# DOORLOCK_v2.net
KiCad netlist of a schematic drawn in EAGLE
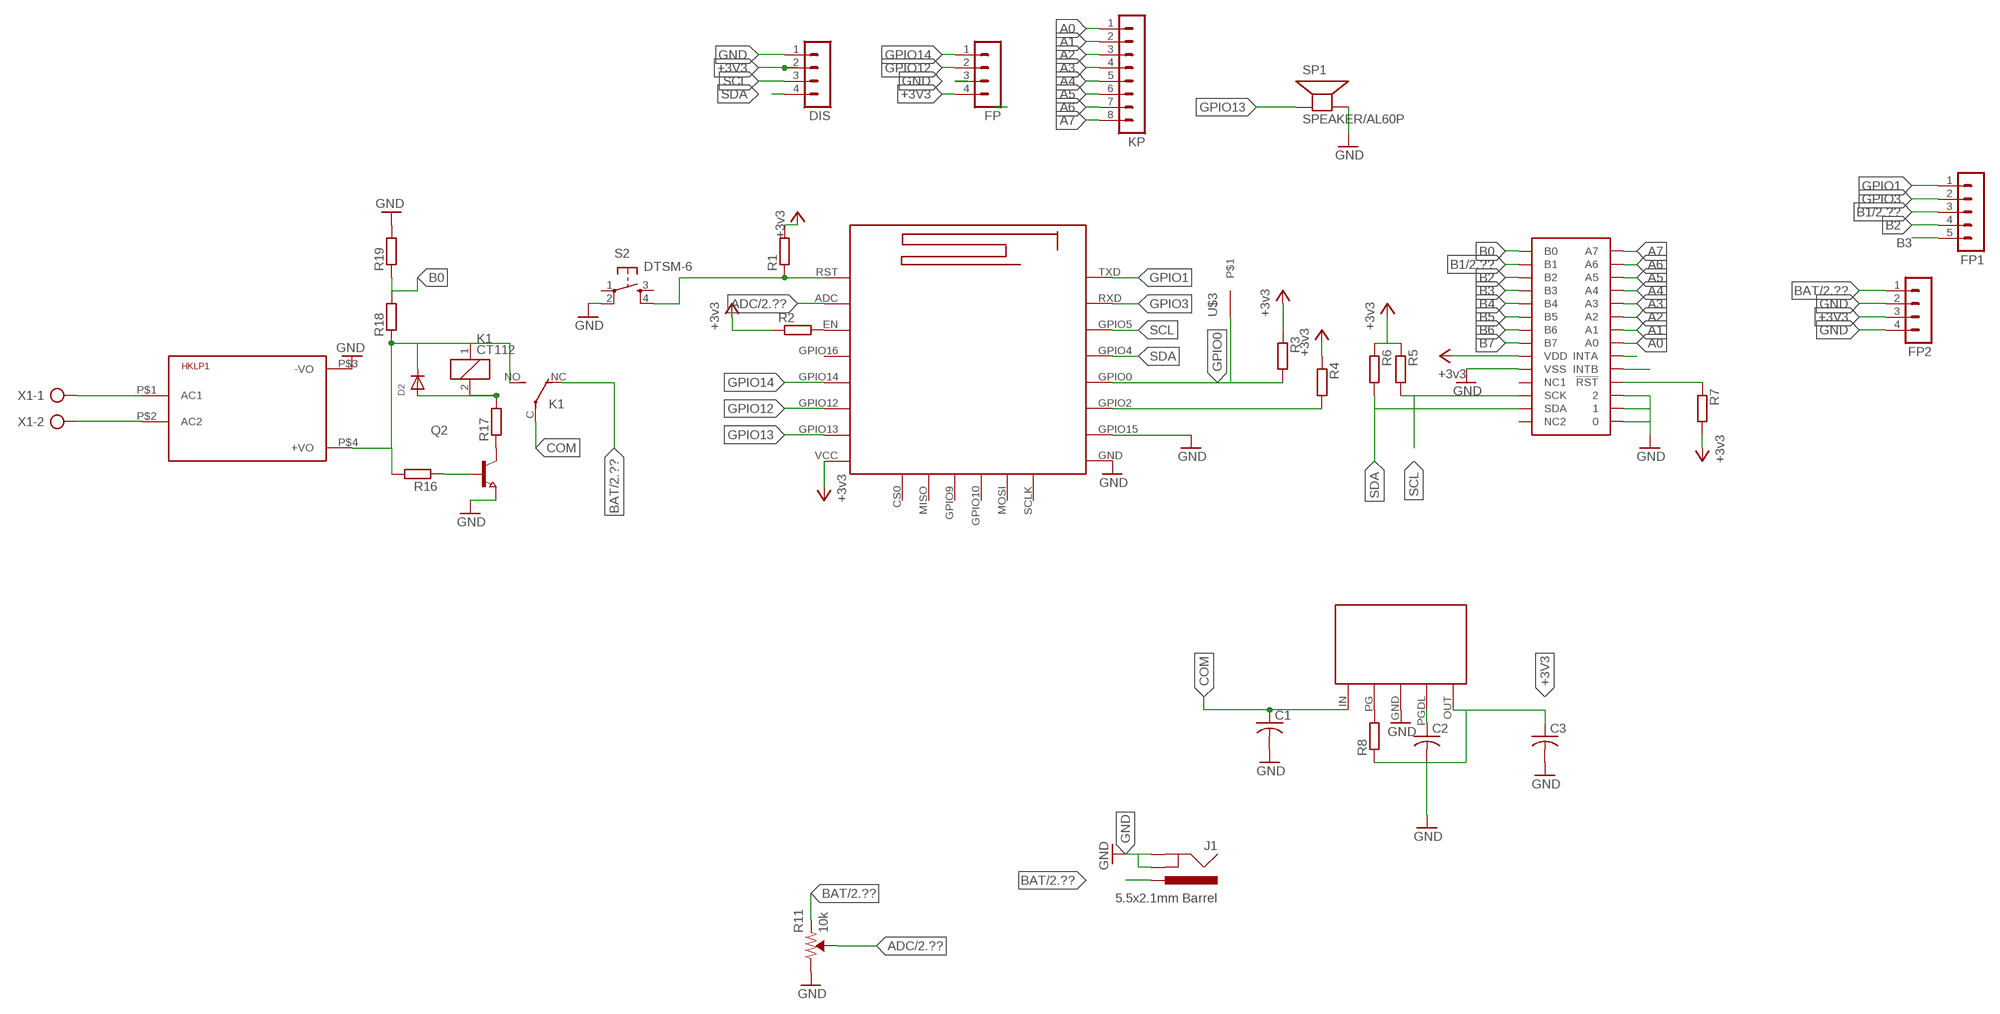
[diagram p0: schematic, sheet 1]
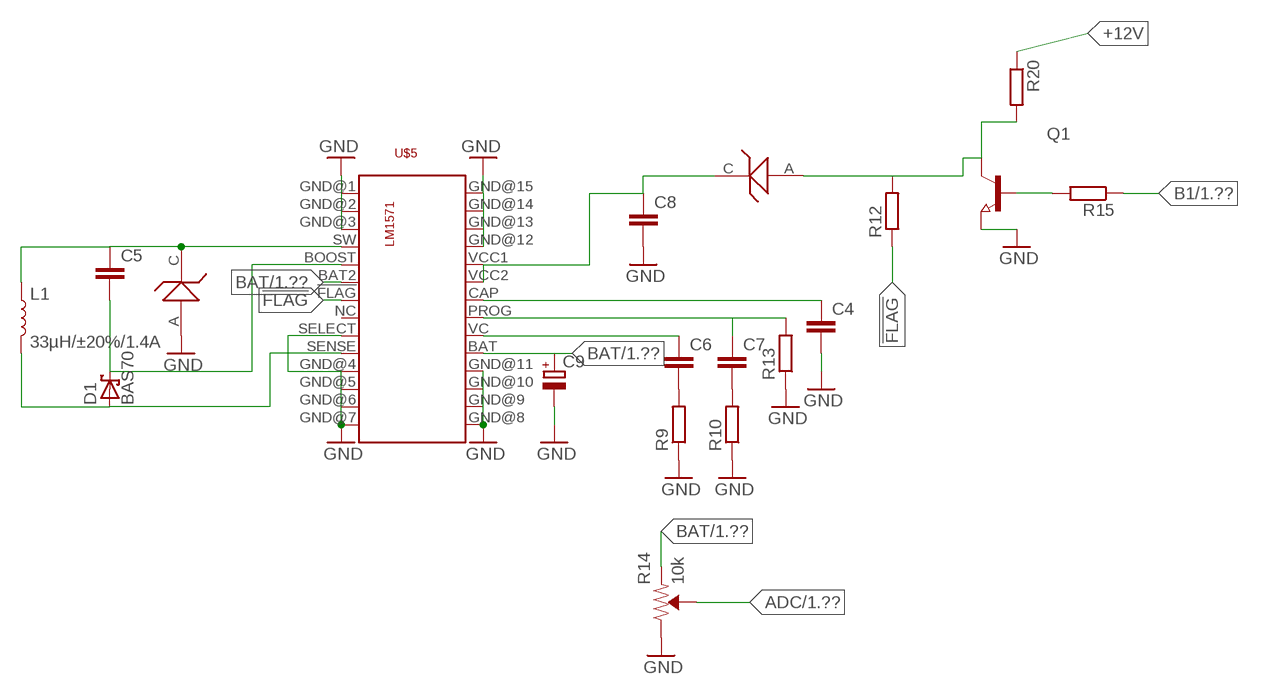
[diagram p1: schematic, sheet 2]

(export (version "E")
  (design (tool "Eeschema 10.0.6"))
  (components
    (comp (ref "C1")
      (value "C-USC1206")
      (footprint "eagle-import:C1206")
      (libsource (lib "eagle-import") (part "C-USC1206"))
    )
    (comp (ref "C2")
      (value "C-USC1206")
      (footprint "eagle-import:C1206")
      (libsource (lib "eagle-import") (part "C-USC1206"))
    )
    (comp (ref "C3")
      (value "C-USC1206")
      (footprint "eagle-import:C1206")
      (libsource (lib "eagle-import") (part "C-USC1206"))
    )
    (comp (ref "D2")
      (value "DIODESOD-123")
      (footprint "eagle-import:SOD-123")
      (libsource (lib "eagle-import") (part "DIODESOD-123"))
    )
    (comp (ref "DIS")
      (value "MA04-1")
      (footprint "eagle-import:MA04-1")
      (libsource (lib "eagle-import") (part "MA04-1"))
    )
    (comp (ref "FP")
      (value "MA04-1")
      (footprint "eagle-import:MA04-1")
      (libsource (lib "eagle-import") (part "MA04-1"))
    )
    (comp (ref "FP1")
      (value "MA05-1")
      (footprint "eagle-import:MA05-1")
      (libsource (lib "eagle-import") (part "MA05-1"))
    )
    (comp (ref "FP2")
      (value "MA04-1")
      (footprint "eagle-import:MA04-1")
      (libsource (lib "eagle-import") (part "MA04-1"))
    )
    (comp (ref "HKLP1")
      (value "HKLPM01")
      (footprint "eagle-import:HKLPM01")
      (libsource (lib "eagle-import") (part "HKLPM01"))
    )
    (comp (ref "J1")
      (value "5.5x2.1mm Barrel")
      (footprint "eagle-import:POWER_JACK_SMD")
      (libsource (lib "eagle-import") (part "POWER_JACKSMD"))
    )
    (comp (ref "K1")
      (value "CT112")
      (footprint "eagle-import:CT-SLIM")
      (libsource (lib "eagle-import") (part "CT112"))
    )
    (comp (ref "KP")
      (value "MA08-1")
      (footprint "eagle-import:MA08-1")
      (libsource (lib "eagle-import") (part "MA08-1"))
    )
    (comp (ref "Q2")
      (value "NPN-TRANSISTOR_SOT89")
      (footprint "eagle-import:SOT89")
      (libsource (lib "eagle-import") (part "NPN-TRANSISTOR_SOT89"))
    )
    (comp (ref "R1")
      (value "R-EU_0204/2V")
      (footprint "eagle-import:0204V")
      (libsource (lib "eagle-import") (part "resistor_R-EU_0204/2V"))
    )
    (comp (ref "R2")
      (value "R-EU_0204/2V")
      (footprint "eagle-import:0204V")
      (libsource (lib "eagle-import") (part "resistor_R-EU_0204/2V"))
    )
    (comp (ref "R3")
      (value "R-EU_0204/2V")
      (footprint "eagle-import:0204V")
      (libsource (lib "eagle-import") (part "resistor_R-EU_0204/2V"))
    )
    (comp (ref "R4")
      (value "R-EU_0204/2V")
      (footprint "eagle-import:0204V")
      (libsource (lib "eagle-import") (part "resistor_R-EU_0204/2V"))
    )
    (comp (ref "R5")
      (value "R-EU_0204/2V")
      (footprint "eagle-import:0204V")
      (libsource (lib "eagle-import") (part "resistor_R-EU_0204/2V"))
    )
    (comp (ref "R6")
      (value "R-EU_0204/2V")
      (footprint "eagle-import:0204V")
      (libsource (lib "eagle-import") (part "resistor_R-EU_0204/2V"))
    )
    (comp (ref "R7")
      (value "R-EU_0204/2V")
      (footprint "eagle-import:0204V")
      (libsource (lib "eagle-import") (part "resistor_R-EU_0204/2V"))
    )
    (comp (ref "R8")
      (value "R-EU_0204/2V")
      (footprint "eagle-import:0204V")
      (libsource (lib "eagle-import") (part "resistor_R-EU_0204/2V"))
    )
    (comp (ref "R11")
      (value "10k")
      (footprint "eagle-import:TRIMPOT-SMD-TC33X")
      (libsource (lib "eagle-import") (part "TRIMPOT-SMD-3MM-OPEN-1/10W-25%"))
    )
    (comp (ref "R16")
      (value "R-EU_0204/2V")
      (footprint "eagle-import:0204V")
      (libsource (lib "eagle-import") (part "resistor_R-EU_0204/2V"))
    )
    (comp (ref "R17")
      (value "R-EU_0204/2V")
      (footprint "eagle-import:0204V")
      (libsource (lib "eagle-import") (part "resistor_R-EU_0204/2V"))
    )
    (comp (ref "R18")
      (value "R-EU_0204/2V")
      (footprint "eagle-import:0204V")
      (libsource (lib "eagle-import") (part "resistor_R-EU_0204/2V"))
    )
    (comp (ref "R19")
      (value "R-EU_0204/2V")
      (footprint "eagle-import:0204V")
      (libsource (lib "eagle-import") (part "resistor_R-EU_0204/2V"))
    )
    (comp (ref "S2")
      (value "DTSM-6")
      (footprint "eagle-import:DTSM-6")
      (libsource (lib "eagle-import") (part "DTSM-6"))
    )
    (comp (ref "SP1")
      (value "SPEAKER/AL60P")
      (footprint "eagle-import:AL60P")
      (libsource (lib "eagle-import") (part "SPEAKER/AL60P"))
    )
    (comp (ref "U$1")
      (value "ESP12E")
      (footprint "eagle-import:ESP-12E")
      (libsource (lib "eagle-import") (part "ESP12E"))
    )
    (comp (ref "U$2")
      (value "MCF23017")
      (footprint "eagle-import:MAX23017")
      (libsource (lib "eagle-import") (part "MCF23017"))
    )
    (comp (ref "U$3") (value "M1") (footprint "eagle-import:M1") (libsource (lib "eagle-import") (part "M1")))
    (comp (ref "U$4")
      (value "MP2014")
      (footprint "eagle-import:MP2014")
      (libsource (lib "eagle-import") (part "MP2014"))
    )
    (comp (ref "X1")
      (value "AK500/2-H")
      (footprint "eagle-import:AK500_2-H")
      (libsource (lib "eagle-import") (part "AK500/2-H"))
    )
    (comp (ref "C4")
      (value "C-EUC0805")
      (footprint "eagle-import:C0805")
      (libsource (lib "eagle-import") (part "C-EUC0805"))
    )
    (comp (ref "C5")
      (value "C-EUC0805")
      (footprint "eagle-import:C0805")
      (libsource (lib "eagle-import") (part "C-EUC0805"))
    )
    (comp (ref "C6")
      (value "C-EUC0805")
      (footprint "eagle-import:C0805")
      (libsource (lib "eagle-import") (part "C-EUC0805"))
    )
    (comp (ref "C7")
      (value "C-EUC0805")
      (footprint "eagle-import:C0805")
      (libsource (lib "eagle-import") (part "C-EUC0805"))
    )
    (comp (ref "C8")
      (value "C-EUC0805")
      (footprint "eagle-import:C0805")
      (libsource (lib "eagle-import") (part "C-EUC0805"))
    )
    (comp (ref "C9")
      (value "CPOL-EUCT3216")
      (footprint "eagle-import:CT3216")
      (libsource (lib "eagle-import") (part "CPOL-EUCT3216"))
    )
    (comp (ref "D1")
      (value "BAS70")
      (footprint "eagle-import:SOT23")
      (libsource (lib "eagle-import") (part "BAS70"))
    )
    (comp (ref "D3")
      (value "MBRM120T3")
      (footprint "eagle-import:MBRM120T3")
      (libsource (lib "eagle-import") (part "MBRM120T3"))
    )
    (comp (ref "L1")
      (value "33µH/±20%/1.4A")
      (footprint "eagle-import:SRN6045")
      (libsource (lib "eagle-import") (part "INDUCTOR-SRN6045-33UH"))
    )
    (comp (ref "Q1")
      (value "NPN-TRANSISTOR_SOT89")
      (footprint "eagle-import:SOT89")
      (libsource (lib "eagle-import") (part "NPN-TRANSISTOR_SOT89"))
    )
    (comp (ref "R9")
      (value "R-EU_0204/2V")
      (footprint "eagle-import:0204V")
      (libsource (lib "eagle-import") (part "R-EU_0204/2V"))
    )
    (comp (ref "R10")
      (value "R-EU_0204/2V")
      (footprint "eagle-import:0204V")
      (libsource (lib "eagle-import") (part "R-EU_0204/2V"))
    )
    (comp (ref "R12")
      (value "R-EU_0204/2V")
      (footprint "eagle-import:0204V")
      (libsource (lib "eagle-import") (part "R-EU_0204/2V"))
    )
    (comp (ref "R13")
      (value "R-EU_0204/2V")
      (footprint "eagle-import:0204V")
      (libsource (lib "eagle-import") (part "R-EU_0204/2V"))
    )
    (comp (ref "R14")
      (value "10k")
      (footprint "eagle-import:TRIMPOT-SMD-TC33X")
      (libsource (lib "eagle-import") (part "TRIMPOT-SMD-3MM-OPEN-1/10W-25%"))
    )
    (comp (ref "R15")
      (value "R-EU_0204/2V")
      (footprint "eagle-import:0204V")
      (libsource (lib "eagle-import") (part "R-EU_0204/2V"))
    )
    (comp (ref "R20")
      (value "R-EU_0204/2V")
      (footprint "eagle-import:0204V")
      (libsource (lib "eagle-import") (part "R-EU_0204/2V"))
    )
    (comp (ref "U$5")
      (value "LM1571")
      (footprint "eagle-import:LT1571")
      (libsource (lib "eagle-import") (part "LM1571"))
    )
    (comp (ref "U$6")
      (value "MBRM120T3")
      (footprint "eagle-import:MBRM120T3")
      (libsource (lib "eagle-import") (part "MBRM120T3"))
    )
  )
  (nets
    (net (code "1") (name "+3V3") (class "Default")
      (node (ref "C3") (pin "1") (pinfunction "1_1") (pintype "passive"))
      (node (ref "DIS") (pin "2") (pinfunction "2_2") (pintype "passive"))
      (node (ref "FP") (pin "4") (pinfunction "4_4") (pintype "passive"))
      (node (ref "FP2") (pin "3") (pinfunction "3_3") (pintype "passive"))
      (node (ref "R1") (pin "2") (pinfunction "2_2") (pintype "passive"))
      (node (ref "R2") (pin "1") (pinfunction "1_1") (pintype "passive"))
      (node (ref "R3") (pin "1") (pinfunction "1_1") (pintype "passive"))
      (node (ref "R4") (pin "1") (pinfunction "1_1") (pintype "passive"))
      (node (ref "R5") (pin "1") (pinfunction "1_1") (pintype "passive"))
      (node (ref "R6") (pin "1") (pinfunction "1_1") (pintype "passive"))
      (node (ref "R7") (pin "2") (pinfunction "2_2") (pintype "passive"))
      (node (ref "R8") (pin "1") (pinfunction "1_1") (pintype "passive"))
      (node (ref "U$1") (pin "VCC") (pinfunction "P$8_VCC") (pintype "bidirectional"))
      (node (ref "U$2") (pin "P$9") (pinfunction "VDD_P$9") (pintype "bidirectional"))
      (node (ref "U$4") (pin "OUT") (pinfunction "P$5_OUT") (pintype "bidirectional"))
    )
    (net (code "2") (name "+12V") (class "Default")
      (node (ref "D2") (pin "C") (pinfunction "C_C") (pintype "passive"))
      (node (ref "HKLP1") (pin "P$4") (pinfunction "+VO_P$4") (pintype "bidirectional"))
      (node (ref "K1") (pin "1") (pinfunction "1_1") (pintype "passive"))
      (node (ref "K1") (pin "NO") (pinfunction "S_NO") (pintype "passive"))
      (node (ref "R16") (pin "2") (pinfunction "2_2") (pintype "passive"))
      (node (ref "R18") (pin "1") (pinfunction "1_1") (pintype "passive"))
      (node (ref "R20") (pin "1") (pinfunction "1_1") (pintype "passive"))
    )
    (net (code "3") (name "A0") (class "Default")
      (node (ref "KP") (pin "1") (pinfunction "1_1") (pintype "passive"))
      (node (ref "U$2") (pin "P$21") (pinfunction "A0_P$21") (pintype "bidirectional"))
    )
    (net (code "4") (name "A1") (class "Default")
      (node (ref "KP") (pin "2") (pinfunction "2_2") (pintype "passive"))
      (node (ref "U$2") (pin "P$22") (pinfunction "A1_P$22") (pintype "bidirectional"))
    )
    (net (code "5") (name "A2") (class "Default")
      (node (ref "KP") (pin "3") (pinfunction "3_3") (pintype "passive"))
      (node (ref "U$2") (pin "P$23") (pinfunction "A2_P$23") (pintype "bidirectional"))
    )
    (net (code "6") (name "A3") (class "Default")
      (node (ref "KP") (pin "4") (pinfunction "4_4") (pintype "passive"))
      (node (ref "U$2") (pin "P$24") (pinfunction "A3_P$24") (pintype "bidirectional"))
    )
    (net (code "7") (name "A4") (class "Default")
      (node (ref "KP") (pin "5") (pinfunction "5_5") (pintype "passive"))
      (node (ref "U$2") (pin "P$25") (pinfunction "A4_P$25") (pintype "bidirectional"))
    )
    (net (code "8") (name "A5") (class "Default")
      (node (ref "KP") (pin "6") (pinfunction "6_6") (pintype "passive"))
      (node (ref "U$2") (pin "P$26") (pinfunction "A5_P$26") (pintype "bidirectional"))
    )
    (net (code "9") (name "A6") (class "Default")
      (node (ref "KP") (pin "7") (pinfunction "7_7") (pintype "passive"))
      (node (ref "U$2") (pin "P$27") (pinfunction "A6_P$27") (pintype "bidirectional"))
    )
    (net (code "10") (name "A7") (class "Default")
      (node (ref "KP") (pin "8") (pinfunction "8_8") (pintype "passive"))
      (node (ref "U$2") (pin "P$28") (pinfunction "A7_P$28") (pintype "bidirectional"))
    )
    (net (code "11") (name "ADC") (class "Default")
      (node (ref "R11") (pin "2") (pinfunction "WIPER_2") (pintype "passive"))
      (node (ref "R14") (pin "2") (pinfunction "WIPER_2") (pintype "passive"))
      (node (ref "U$1") (pin "ADC") (pinfunction "P$2_ADC") (pintype "bidirectional"))
    )
    (net (code "12") (name "B0") (class "Default")
      (node (ref "R18") (pin "2") (pinfunction "2_2") (pintype "passive"))
      (node (ref "R19") (pin "1") (pinfunction "1_1") (pintype "passive"))
      (node (ref "U$2") (pin "P$1") (pinfunction "B0_P$1") (pintype "bidirectional"))
    )
    (net (code "13") (name "B1") (class "Default")
      (node (ref "FP1") (pin "3") (pinfunction "3_3") (pintype "passive"))
      (node (ref "R15") (pin "1") (pinfunction "1_1") (pintype "passive"))
      (node (ref "U$2") (pin "P$2") (pinfunction "B1_P$2") (pintype "bidirectional"))
    )
    (net (code "14") (name "B2") (class "Default")
      (node (ref "FP1") (pin "4") (pinfunction "4_4") (pintype "passive"))
      (node (ref "U$2") (pin "P$3") (pinfunction "B2_P$3") (pintype "bidirectional"))
    )
    (net (code "15") (name "B3") (class "Default")
      (node (ref "FP1") (pin "5") (pinfunction "5_5") (pintype "passive"))
      (node (ref "U$2") (pin "P$4") (pinfunction "B3_P$4") (pintype "bidirectional"))
    )
    (net (code "16") (name "B4") (class "Default")
      (node (ref "U$2") (pin "P$5") (pinfunction "B4_P$5") (pintype "bidirectional"))
    )
    (net (code "17") (name "B5") (class "Default")
      (node (ref "U$2") (pin "P$6") (pinfunction "B5_P$6") (pintype "bidirectional"))
    )
    (net (code "18") (name "B6") (class "Default")
      (node (ref "U$2") (pin "P$7") (pinfunction "B6_P$7") (pintype "bidirectional"))
    )
    (net (code "19") (name "B7") (class "Default")
      (node (ref "U$2") (pin "P$8") (pinfunction "B7_P$8") (pintype "bidirectional"))
    )
    (net (code "20") (name "BAT") (class "Default")
      (node (ref "C9") (pin "+") (pinfunction "+_+") (pintype "passive"))
      (node (ref "FP2") (pin "1") (pinfunction "1_1") (pintype "passive"))
      (node (ref "J1") (pin "VIN0") (pinfunction "PWR_VIN0") (pintype "bidirectional"))
      (node (ref "K1") (pin "NC") (pinfunction "O_NC") (pintype "passive"))
      (node (ref "R11") (pin "3") (pinfunction "CCW_3") (pintype "passive"))
      (node (ref "R14") (pin "3") (pinfunction "CCW_3") (pintype "passive"))
      (node (ref "U$5") (pin "BAT") (pinfunction "P$19_BAT") (pintype "bidirectional"))
      (node (ref "U$5") (pin "BAT2") (pinfunction "P$6_BAT2") (pintype "bidirectional"))
    )
    (net (code "21") (name "COM") (class "Default")
      (node (ref "C1") (pin "1") (pinfunction "1_1") (pintype "passive"))
      (node (ref "K1") (pin "C") (pinfunction "P_C") (pintype "passive"))
      (node (ref "U$4") (pin "IN") (pinfunction "P$1_IN") (pintype "bidirectional"))
    )
    (net (code "22") (name "GND") (class "Default")
      (node (ref "C1") (pin "2") (pinfunction "2_2") (pintype "passive"))
      (node (ref "C2") (pin "2") (pinfunction "2_2") (pintype "passive"))
      (node (ref "C3") (pin "2") (pinfunction "2_2") (pintype "passive"))
      (node (ref "C4") (pin "2") (pinfunction "2_2") (pintype "passive"))
      (node (ref "C8") (pin "2") (pinfunction "2_2") (pintype "passive"))
      (node (ref "C9") (pin "-") (pinfunction "-_-") (pintype "passive"))
      (node (ref "DIS") (pin "1") (pinfunction "1_1") (pintype "passive"))
      (node (ref "FP") (pin "3") (pinfunction "3_3") (pintype "passive"))
      (node (ref "FP2") (pin "2") (pinfunction "2_2") (pintype "passive"))
      (node (ref "FP2") (pin "4") (pinfunction "4_4") (pintype "passive"))
      (node (ref "HKLP1") (pin "P$3") (pinfunction "-VO_P$3") (pintype "bidirectional"))
      (node (ref "J1") (pin "GND") (pinfunction "GNDBREAK_GND") (pintype "bidirectional"))
      (node (ref "J1") (pin "P$4") (pinfunction "GND_P$4") (pintype "bidirectional"))
      (node (ref "Q1") (pin "3") (pinfunction "E_3") (pintype "passive"))
      (node (ref "Q2") (pin "3") (pinfunction "E_3") (pintype "passive"))
      (node (ref "R10") (pin "1") (pinfunction "1_1") (pintype "passive"))
      (node (ref "R11") (pin "1") (pinfunction "CW_1") (pintype "passive"))
      (node (ref "R13") (pin "1") (pinfunction "1_1") (pintype "passive"))
      (node (ref "R14") (pin "1") (pinfunction "CW_1") (pintype "passive"))
      (node (ref "R19") (pin "2") (pinfunction "2_2") (pintype "passive"))
      (node (ref "R9") (pin "1") (pinfunction "1_1") (pintype "passive"))
      (node (ref "S2") (pin "2") (pinfunction "2_2") (pintype "passive"))
      (node (ref "SP1") (pin "2") (pinfunction "-_2") (pintype "passive"))
      (node (ref "U$1") (pin "GND") (pinfunction "P$15_GND") (pintype "bidirectional"))
      (node (ref "U$1") (pin "GPIO15") (pinfunction "P$16_GPIO15") (pintype "bidirectional"))
      (node (ref "U$2") (pin "P$10") (pinfunction "VSS_P$10") (pintype "bidirectional"))
      (node (ref "U$2") (pin "P$15") (pinfunction "0_P$15") (pintype "bidirectional"))
      (node (ref "U$2") (pin "P$16") (pinfunction "1_P$16") (pintype "bidirectional"))
      (node (ref "U$2") (pin "P$17") (pinfunction "2_P$17") (pintype "bidirectional"))
      (node (ref "U$4") (pin "GND") (pinfunction "P$3_GND") (pintype "bidirectional"))
      (node (ref "U$5") (pin "GND@1") (pinfunction "P$1_GND@1") (pintype "bidirectional"))
      (node (ref "U$5") (pin "GND@10") (pinfunction "P$17_GND@10") (pintype "bidirectional"))
      (node (ref "U$5") (pin "GND@11") (pinfunction "P$18_GND@11") (pintype "bidirectional"))
      (node (ref "U$5") (pin "GND@12") (pinfunction "P$25_GND@12") (pintype "bidirectional"))
      (node (ref "U$5") (pin "GND@13") (pinfunction "P$26_GND@13") (pintype "bidirectional"))
      (node (ref "U$5") (pin "GND@14") (pinfunction "P$27_GND@14") (pintype "bidirectional"))
      (node (ref "U$5") (pin "GND@15") (pinfunction "P$28_GND@15") (pintype "bidirectional"))
      (node (ref "U$5") (pin "GND@2") (pinfunction "P$2_GND@2") (pintype "bidirectional"))
      (node (ref "U$5") (pin "GND@3") (pinfunction "P$3_GND@3") (pintype "bidirectional"))
      (node (ref "U$5") (pin "GND@4") (pinfunction "P$11_GND@4") (pintype "bidirectional"))
      (node (ref "U$5") (pin "GND@5") (pinfunction "P$12_GND@5") (pintype "bidirectional"))
      (node (ref "U$5") (pin "GND@6") (pinfunction "P$13_GND@6") (pintype "bidirectional"))
      (node (ref "U$5") (pin "GND@7") (pinfunction "P$14_GND@7") (pintype "bidirectional"))
      (node (ref "U$5") (pin "GND@8") (pinfunction "P$15_GND@8") (pintype "bidirectional"))
      (node (ref "U$5") (pin "GND@9") (pinfunction "P$16_GND@9") (pintype "bidirectional"))
      (node (ref "U$5") (pin "SELECT") (pinfunction "P$9_SELECT") (pintype "bidirectional"))
      (node (ref "U$6") (pin "A") (pinfunction "A_A") (pintype "bidirectional"))
    )
    (net (code "23") (name "GPIO0") (class "Default")
      (node (ref "R3") (pin "2") (pinfunction "2_2") (pintype "passive"))
      (node (ref "U$1") (pin "GPIO0") (pinfunction "P$18_GPIO0") (pintype "bidirectional"))
      (node (ref "U$3") (pin "P$1") (pinfunction "P$1_P$1") (pintype "bidirectional"))
    )
    (net (code "24") (name "GPIO1") (class "Default")
      (node (ref "FP1") (pin "1") (pinfunction "1_1") (pintype "passive"))
      (node (ref "U$1") (pin "TXD") (pinfunction "P$22_TXD") (pintype "bidirectional"))
    )
    (net (code "25") (name "GPIO3") (class "Default")
      (node (ref "FP1") (pin "2") (pinfunction "2_2") (pintype "passive"))
      (node (ref "U$1") (pin "RXD") (pinfunction "P$21_RXD") (pintype "bidirectional"))
    )
    (net (code "26") (name "GPIO12") (class "Default")
      (node (ref "FP") (pin "2") (pinfunction "2_2") (pintype "passive"))
      (node (ref "U$1") (pin "GPIO12") (pinfunction "P$6_GPIO12") (pintype "bidirectional"))
    )
    (net (code "27") (name "GPIO13") (class "Default")
      (node (ref "SP1") (pin "1") (pinfunction "+_1") (pintype "passive"))
      (node (ref "U$1") (pin "GPIO13") (pinfunction "P$7_GPIO13") (pintype "bidirectional"))
    )
    (net (code "28") (name "GPIO14") (class "Default")
      (node (ref "FP") (pin "1") (pinfunction "1_1") (pintype "passive"))
      (node (ref "U$1") (pin "GPIO14") (pinfunction "P$5_GPIO14") (pintype "bidirectional"))
    )
    (net (code "29") (name "Net-(C6-Pad2)") (class "Default")
      (node (ref "C6") (pin "2") (pinfunction "2_2") (pintype "passive"))
      (node (ref "R9") (pin "2") (pinfunction "2_2") (pintype "passive"))
    )
    (net (code "30") (name "Net-(C7-Pad2)") (class "Default")
      (node (ref "C7") (pin "2") (pinfunction "2_2") (pintype "passive"))
      (node (ref "R10") (pin "2") (pinfunction "2_2") (pintype "passive"))
    )
    (net (code "31") (name "Net-(D1-A)") (class "Default")
      (node (ref "D1") (pin "1") (pinfunction "A_1") (pintype "passive"))
      (node (ref "L1") (pin "2") (pinfunction "2_2") (pintype "passive"))
      (node (ref "U$5") (pin "SENSE") (pinfunction "P$10_SENSE") (pintype "bidirectional"))
    )
    (net (code "32") (name "Net-(D1-C)") (class "Default")
      (node (ref "C5") (pin "2") (pinfunction "2_2") (pintype "passive"))
      (node (ref "D1") (pin "3") (pinfunction "C_3") (pintype "passive"))
      (node (ref "U$5") (pin "BOOST") (pinfunction "P$5_BOOST") (pintype "bidirectional"))
    )
    (net (code "33") (name "Net-(D2-PadA)") (class "Default")
      (node (ref "D2") (pin "A") (pinfunction "A_A") (pintype "passive"))
      (node (ref "K1") (pin "2") (pinfunction "2_2") (pintype "passive"))
      (node (ref "R17") (pin "2") (pinfunction "2_2") (pintype "passive"))
    )
    (net (code "34") (name "Net-(HKLP1-AC1)") (class "Default")
      (node (ref "HKLP1") (pin "P$1") (pinfunction "AC1_P$1") (pintype "bidirectional"))
      (node (ref "X1") (pin "1") (pinfunction "KL_1") (pintype "passive"))
    )
    (net (code "35") (name "Net-(HKLP1-AC2)") (class "Default")
      (node (ref "HKLP1") (pin "P$2") (pinfunction "AC2_P$2") (pintype "bidirectional"))
      (node (ref "X1") (pin "2") (pinfunction "KL_2") (pintype "passive"))
    )
    (net (code "36") (name "Net-(Q1-B)") (class "Default")
      (node (ref "Q1") (pin "1") (pinfunction "B_1") (pintype "passive"))
      (node (ref "R15") (pin "2") (pinfunction "2_2") (pintype "passive"))
    )
    (net (code "37") (name "Net-(Q1-C)") (class "Default")
      (node (ref "D3") (pin "A") (pinfunction "A_A") (pintype "bidirectional"))
      (node (ref "Q1") (pin "2") (pinfunction "C_2") (pintype "passive"))
      (node (ref "R12") (pin "2") (pinfunction "2_2") (pintype "passive"))
      (node (ref "R20") (pin "2") (pinfunction "2_2") (pintype "passive"))
    )
    (net (code "38") (name "Net-(Q2-B)") (class "Default")
      (node (ref "Q2") (pin "1") (pinfunction "B_1") (pintype "passive"))
      (node (ref "R16") (pin "1") (pinfunction "1_1") (pintype "passive"))
    )
    (net (code "39") (name "Net-(Q2-C)") (class "Default")
      (node (ref "Q2") (pin "2") (pinfunction "C_2") (pintype "passive"))
      (node (ref "R17") (pin "1") (pinfunction "1_1") (pintype "passive"))
    )
    (net (code "40") (name "Net-(U$1-P$1)") (class "Default")
      (node (ref "R1") (pin "1") (pinfunction "1_1") (pintype "passive"))
      (node (ref "S2") (pin "4") (pinfunction "4_4") (pintype "passive"))
      (node (ref "U$1") (pin "RST") (pinfunction "P$1_RST") (pintype "bidirectional"))
    )
    (net (code "41") (name "Net-(U$1-P$3)") (class "Default")
      (node (ref "R2") (pin "2") (pinfunction "2_2") (pintype "passive"))
      (node (ref "U$1") (pin "EN") (pinfunction "P$3_EN") (pintype "bidirectional"))
    )
    (net (code "42") (name "Net-(U$1-P$17)") (class "Default")
      (node (ref "R4") (pin "2") (pinfunction "2_2") (pintype "passive"))
      (node (ref "U$1") (pin "GPIO2") (pinfunction "P$17_GPIO2") (pintype "bidirectional"))
    )
    (net (code "43") (name "Net-(U$2-~{RST})") (class "Default")
      (node (ref "R7") (pin "1") (pinfunction "1_1") (pintype "passive"))
      (node (ref "U$2") (pin "P$18") (pinfunction "~{RST}_P$18") (pintype "bidirectional"))
    )
    (net (code "44") (name "Net-(U$4-P$2)") (class "Default")
      (node (ref "R8") (pin "2") (pinfunction "2_2") (pintype "passive"))
      (node (ref "U$4") (pin "PG") (pinfunction "P$2_PG") (pintype "bidirectional"))
    )
    (net (code "45") (name "Net-(U$4-P$4)") (class "Default")
      (node (ref "C2") (pin "1") (pinfunction "1_1") (pintype "passive"))
      (node (ref "U$4") (pin "PGDL") (pinfunction "P$4_PGDL") (pintype "bidirectional"))
    )
    (net (code "46") (name "Net-(U$5-P$4)") (class "Default")
      (node (ref "C5") (pin "1") (pinfunction "1_1") (pintype "passive"))
      (node (ref "L1") (pin "1") (pinfunction "1_1") (pintype "passive"))
      (node (ref "U$5") (pin "SW") (pinfunction "P$4_SW") (pintype "bidirectional"))
      (node (ref "U$6") (pin "C") (pinfunction "C_C") (pintype "bidirectional"))
    )
    (net (code "47") (name "Net-(U$5-P$20)") (class "Default")
      (node (ref "C6") (pin "1") (pinfunction "1_1") (pintype "passive"))
      (node (ref "U$5") (pin "VC") (pinfunction "P$20_VC") (pintype "bidirectional"))
    )
    (net (code "48") (name "Net-(U$5-P$21)") (class "Default")
      (node (ref "C7") (pin "1") (pinfunction "1_1") (pintype "passive"))
      (node (ref "R13") (pin "2") (pinfunction "2_2") (pintype "passive"))
      (node (ref "U$5") (pin "PROG") (pinfunction "P$21_PROG") (pintype "bidirectional"))
    )
    (net (code "49") (name "Net-(U$5-P$22)") (class "Default")
      (node (ref "C4") (pin "1") (pinfunction "1_1") (pintype "passive"))
      (node (ref "U$5") (pin "CAP") (pinfunction "P$22_CAP") (pintype "bidirectional"))
    )
    (net (code "50") (name "Net-(U$5-P$23)") (class "Default")
      (node (ref "C8") (pin "1") (pinfunction "1_1") (pintype "passive"))
      (node (ref "D3") (pin "C") (pinfunction "C_C") (pintype "bidirectional"))
      (node (ref "U$5") (pin "VCC1") (pinfunction "P$24_VCC1") (pintype "bidirectional"))
      (node (ref "U$5") (pin "VCC2") (pinfunction "P$23_VCC2") (pintype "bidirectional"))
    )
    (net (code "51") (name "SCL") (class "Default")
      (node (ref "DIS") (pin "3") (pinfunction "3_3") (pintype "passive"))
      (node (ref "R5") (pin "2") (pinfunction "2_2") (pintype "passive"))
      (node (ref "U$1") (pin "GPIO5") (pinfunction "P$20_GPIO5") (pintype "bidirectional"))
      (node (ref "U$2") (pin "P$12") (pinfunction "SCK_P$12") (pintype "bidirectional"))
    )
    (net (code "52") (name "SDA") (class "Default")
      (node (ref "DIS") (pin "4") (pinfunction "4_4") (pintype "passive"))
      (node (ref "R6") (pin "2") (pinfunction "2_2") (pintype "passive"))
      (node (ref "U$1") (pin "GPIO4") (pinfunction "P$19_GPIO4") (pintype "bidirectional"))
      (node (ref "U$2") (pin "P$13") (pinfunction "SDA_P$13") (pintype "bidirectional"))
    )
    (net (code "53") (name "unconnected-(S2-Pad1)") (class "Default")
      (node (ref "S2") (pin "1") (pinfunction "1_1") (pintype "passive"))
    )
    (net (code "54") (name "unconnected-(S2-Pad3)") (class "Default")
      (node (ref "S2") (pin "3") (pinfunction "3_3") (pintype "passive"))
    )
    (net (code "55") (name "unconnected-(U$1-P$4-PadGPIO16)") (class "Default")
      (node (ref "U$1") (pin "GPIO16") (pinfunction "P$4_GPIO16") (pintype "bidirectional"))
    )
    (net (code "56") (name "unconnected-(U$1-P$9-PadCS0)") (class "Default")
      (node (ref "U$1") (pin "CS0") (pinfunction "P$9_CS0") (pintype "bidirectional"))
    )
    (net (code "57") (name "unconnected-(U$1-P$10-PadMISO)") (class "Default")
      (node (ref "U$1") (pin "MISO") (pinfunction "P$10_MISO") (pintype "bidirectional"))
    )
    (net (code "58") (name "unconnected-(U$1-P$11-PadGPIO9)") (class "Default")
      (node (ref "U$1") (pin "GPIO9") (pinfunction "P$11_GPIO9") (pintype "bidirectional"))
    )
    (net (code "59") (name "unconnected-(U$1-P$12-PadGPIO10)") (class "Default")
      (node (ref "U$1") (pin "GPIO10") (pinfunction "P$12_GPIO10") (pintype "bidirectional"))
    )
    (net (code "60") (name "unconnected-(U$1-P$13-PadMOSI)") (class "Default")
      (node (ref "U$1") (pin "MOSI") (pinfunction "P$13_MOSI") (pintype "bidirectional"))
    )
    (net (code "61") (name "unconnected-(U$1-P$14-PadSCLK)") (class "Default")
      (node (ref "U$1") (pin "SCLK") (pinfunction "P$14_SCLK") (pintype "bidirectional"))
    )
    (net (code "62") (name "unconnected-(U$2-INTA-PadP$20)") (class "Default")
      (node (ref "U$2") (pin "P$20") (pinfunction "INTA_P$20") (pintype "bidirectional"))
    )
    (net (code "63") (name "unconnected-(U$2-INTB-PadP$19)") (class "Default")
      (node (ref "U$2") (pin "P$19") (pinfunction "INTB_P$19") (pintype "bidirectional"))
    )
    (net (code "64") (name "unconnected-(U$2-NC1-PadP$11)") (class "Default")
      (node (ref "U$2") (pin "P$11") (pinfunction "NC1_P$11") (pintype "bidirectional"))
    )
    (net (code "65") (name "unconnected-(U$2-NC2-PadP$14)") (class "Default")
      (node (ref "U$2") (pin "P$14") (pinfunction "NC2_P$14") (pintype "bidirectional"))
    )
    (net (code "66") (name "unconnected-(U$5-P$8-PadNC)") (class "Default")
      (node (ref "U$5") (pin "NC") (pinfunction "P$8_NC") (pintype "bidirectional"))
    )
    (net (code "67") (name "~{FLAG}") (class "Default")
      (node (ref "R12") (pin "1") (pinfunction "1_1") (pintype "passive"))
      (node (ref "U$5") (pin "!FLAG") (pinfunction "P$7_!FLAG") (pintype "bidirectional"))
    )
  )
)
